# IR.net
KiCad netlist of a schematic drawn in EAGLE
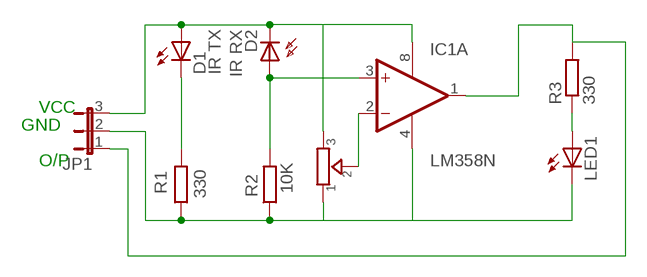
[diagram p0: schematic, sheet 1]

(export (version "E")
  (design (tool "Eeschema 10.0.6"))
  (components
    (comp (ref "D1")
      (value "IR TX")
      (footprint "eagle-import:SFH482")
      (libsource (lib "eagle-import") (part "SFH482"))
    )
    (comp (ref "D2")
      (value "IR RX")
      (footprint "eagle-import:BPW32")
      (libsource (lib "eagle-import") (part "BPW32"))
    )
    (comp (ref "IC1")
      (value "LM358N")
      (footprint "eagle-import:DIL08")
      (libsource (lib "eagle-import") (part "LM358N"))
    )
    (comp (ref "JP1")
      (value "JP2E")
      (footprint "eagle-import:JP2")
      (libsource (lib "eagle-import") (part "JP2E"))
    )
    (comp (ref "LED1")
      (value "LEDLZR181")
      (footprint "eagle-import:LZR181")
      (libsource (lib "eagle-import") (part "LEDLZR181"))
    )
    (comp (ref "R1")
      (value "330")
      (footprint "eagle-import:0204_7")
      (libsource (lib "eagle-import") (part "R0204/7"))
    )
    (comp (ref "R2")
      (value "10K")
      (footprint "eagle-import:0204_7")
      (libsource (lib "eagle-import") (part "R0204/7"))
    )
    (comp (ref "R3")
      (value "330")
      (footprint "eagle-import:0204_7")
      (libsource (lib "eagle-import") (part "R0204/7"))
    )
    (comp (ref "R5")
      (value "TRIMMER-3306F")
      (footprint "eagle-import:TRIMMER_3306F")
      (libsource (lib "eagle-import") (part "TRIMMER-3306F"))
    )
  )
  (nets
    (net (code "1") (name "Net-(D1-C)") (class "Default")
      (node (ref "D1") (pin "K") (pinfunction "C_K") (pintype "passive"))
      (node (ref "R1") (pin "2") (pinfunction "2_2") (pintype "passive"))
    )
    (net (code "2") (name "Net-(D2-C)") (class "Default")
      (node (ref "D1") (pin "A") (pinfunction "A_A") (pintype "passive"))
      (node (ref "D2") (pin "K") (pinfunction "C_K") (pintype "passive"))
      (node (ref "IC1") (pin "8") (pinfunction "V+_8") (pintype "power_in"))
      (node (ref "JP1") (pin "3") (pinfunction "3_3") (pintype "passive"))
      (node (ref "R5") (pin "3") (pinfunction "3_3") (pintype "passive"))
    )
    (net (code "3") (name "Net-(IC1A-+IN)") (class "Default")
      (node (ref "D2") (pin "A") (pinfunction "A_A") (pintype "passive"))
      (node (ref "IC1") (pin "3") (pinfunction "+IN_3") (pintype "input"))
      (node (ref "R2") (pin "2") (pinfunction "2_2") (pintype "passive"))
    )
    (net (code "4") (name "Net-(IC1A--IN)") (class "Default")
      (node (ref "IC1") (pin "2") (pinfunction "-IN_2") (pintype "input"))
      (node (ref "R5") (pin "2") (pinfunction "2_2") (pintype "passive"))
    )
    (net (code "5") (name "Net-(IC1A-OUT)") (class "Default")
      (node (ref "IC1") (pin "1") (pinfunction "OUT_1") (pintype "output"))
      (node (ref "JP1") (pin "1") (pinfunction "1_1") (pintype "passive"))
      (node (ref "R3") (pin "2") (pinfunction "2_2") (pintype "passive"))
    )
    (net (code "6") (name "Net-(IC1C-V-)") (class "Default")
      (node (ref "IC1") (pin "4") (pinfunction "V-_4") (pintype "power_in"))
      (node (ref "JP1") (pin "2") (pinfunction "2_2") (pintype "passive"))
      (node (ref "LED1") (pin "K") (pinfunction "C_K") (pintype "passive"))
      (node (ref "R1") (pin "1") (pinfunction "1_1") (pintype "passive"))
      (node (ref "R2") (pin "1") (pinfunction "1_1") (pintype "passive"))
      (node (ref "R5") (pin "1") (pinfunction "1_1") (pintype "passive"))
    )
    (net (code "7") (name "Net-(LED1-PadA)") (class "Default")
      (node (ref "LED1") (pin "A") (pinfunction "A_A") (pintype "passive"))
      (node (ref "R3") (pin "1") (pinfunction "1_1") (pintype "passive"))
    )
  )
)
